# LED_Strips_-_Schematic.net
KiCad netlist of a schematic drawn in EAGLE
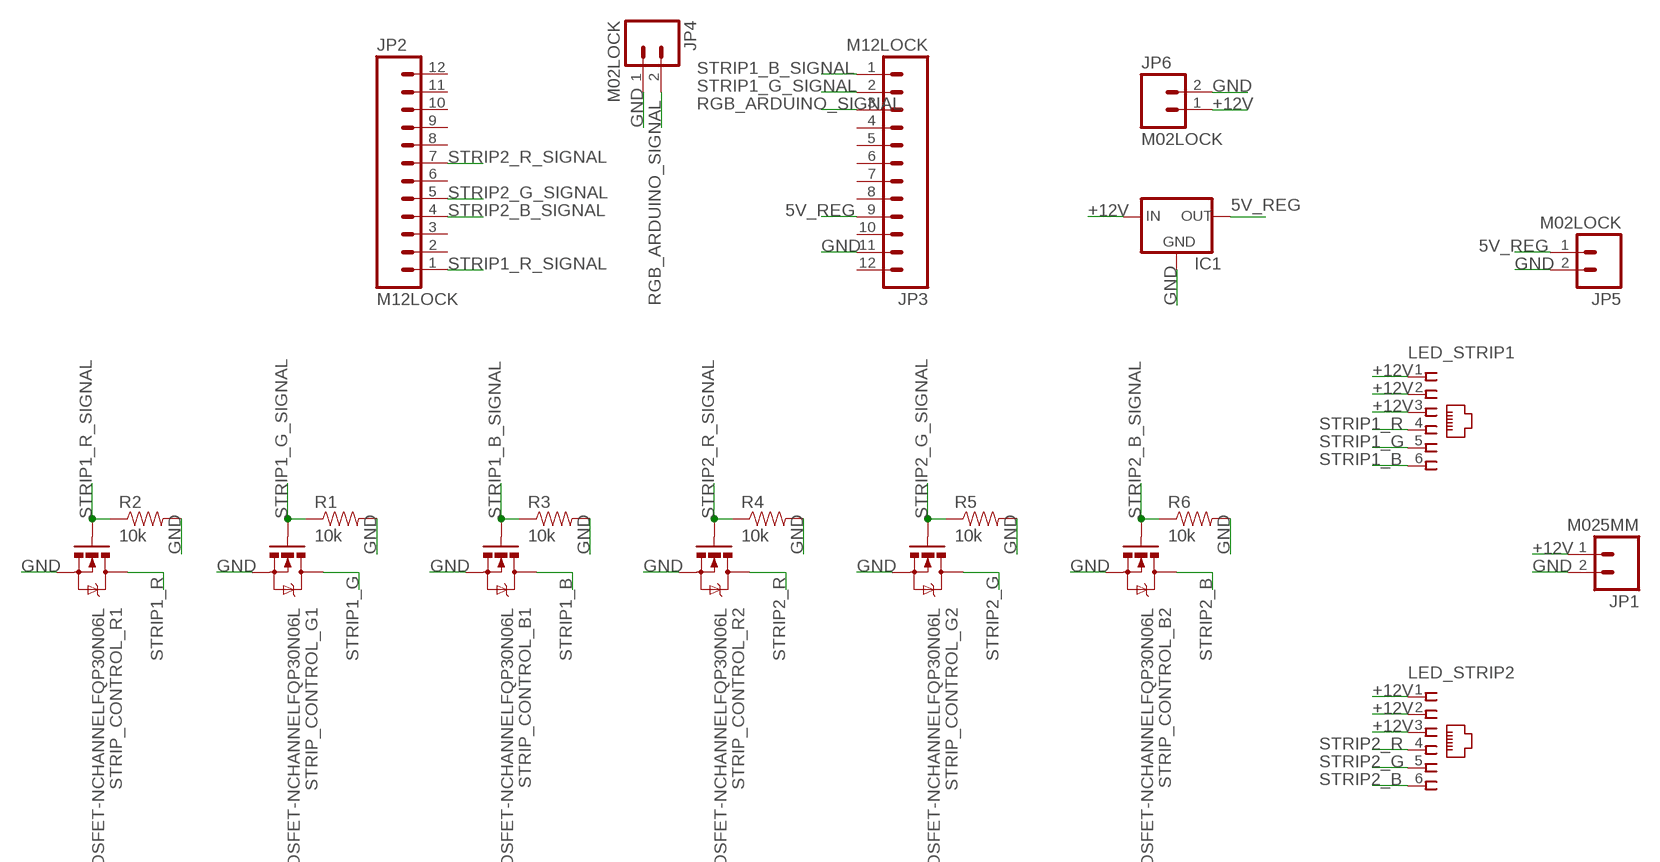
[diagram p0: schematic, sheet 1]

(export (version "E")
  (design (tool "Eeschema 10.0.6"))
  (components
    (comp (ref "IC1")
      (value "V_REG_78XXSIDE")
      (footprint "eagle-import:78XXL")
      (libsource (lib "eagle-import") (part "V_REG_78XXSIDE"))
    )
    (comp (ref "JP1")
      (value "M025MM")
      (footprint "eagle-import:SCREWTERMINAL-5MM-2")
      (libsource (lib "eagle-import") (part "M025MM"))
    )
    (comp (ref "JP2")
      (value "M12LOCK")
      (footprint "eagle-import:1X12_LOCK")
      (libsource (lib "eagle-import") (part "M12LOCK"))
    )
    (comp (ref "JP3")
      (value "M12LOCK")
      (footprint "eagle-import:1X12_LOCK")
      (libsource (lib "eagle-import") (part "M12LOCK"))
    )
    (comp (ref "JP4")
      (value "M02LOCK")
      (footprint "eagle-import:1X02_LOCK")
      (libsource (lib "eagle-import") (part "M02LOCK"))
    )
    (comp (ref "JP5")
      (value "M02LOCK")
      (footprint "eagle-import:1X02_LOCK")
      (libsource (lib "eagle-import") (part "M02LOCK"))
    )
    (comp (ref "JP6")
      (value "M02LOCK")
      (footprint "eagle-import:1X02_LOCK")
      (libsource (lib "eagle-import") (part "M02LOCK"))
    )
    (comp (ref "LED_STRIP1")
      (value "555165-1")
      (footprint "eagle-import:555165-1")
      (libsource (lib "eagle-import") (part "555165-1"))
    )
    (comp (ref "LED_STRIP2")
      (value "555165-1")
      (footprint "eagle-import:555165-1")
      (libsource (lib "eagle-import") (part "555165-1"))
    )
    (comp (ref "R1")
      (value "10k")
      (footprint "eagle-import:0603-RES")
      (libsource (lib "eagle-import") (part "RESISTOR0603"))
    )
    (comp (ref "R2")
      (value "10k")
      (footprint "eagle-import:0603-RES")
      (libsource (lib "eagle-import") (part "RESISTOR0603"))
    )
    (comp (ref "R3")
      (value "10k")
      (footprint "eagle-import:0603-RES")
      (libsource (lib "eagle-import") (part "RESISTOR0603"))
    )
    (comp (ref "R4")
      (value "10k")
      (footprint "eagle-import:0603-RES")
      (libsource (lib "eagle-import") (part "RESISTOR0603"))
    )
    (comp (ref "R5")
      (value "10k")
      (footprint "eagle-import:0603-RES")
      (libsource (lib "eagle-import") (part "RESISTOR0603"))
    )
    (comp (ref "R6")
      (value "10k")
      (footprint "eagle-import:0603-RES")
      (libsource (lib "eagle-import") (part "RESISTOR0603"))
    )
    (comp (ref "STRIP_CONTROL_B1")
      (value "MOSFET-NCHANNELFQP30N06L")
      (footprint "eagle-import:TO220V")
      (libsource (lib "eagle-import") (part "MOSFET-NCHANNELFQP30N06L"))
    )
    (comp (ref "STRIP_CONTROL_B2")
      (value "MOSFET-NCHANNELFQP30N06L")
      (footprint "eagle-import:TO220V")
      (libsource (lib "eagle-import") (part "MOSFET-NCHANNELFQP30N06L"))
    )
    (comp (ref "STRIP_CONTROL_G1")
      (value "MOSFET-NCHANNELFQP30N06L")
      (footprint "eagle-import:TO220V")
      (libsource (lib "eagle-import") (part "MOSFET-NCHANNELFQP30N06L"))
    )
    (comp (ref "STRIP_CONTROL_G2")
      (value "MOSFET-NCHANNELFQP30N06L")
      (footprint "eagle-import:TO220V")
      (libsource (lib "eagle-import") (part "MOSFET-NCHANNELFQP30N06L"))
    )
    (comp (ref "STRIP_CONTROL_R1")
      (value "MOSFET-NCHANNELFQP30N06L")
      (footprint "eagle-import:TO220V")
      (libsource (lib "eagle-import") (part "MOSFET-NCHANNELFQP30N06L"))
    )
    (comp (ref "STRIP_CONTROL_R2")
      (value "MOSFET-NCHANNELFQP30N06L")
      (footprint "eagle-import:TO220V")
      (libsource (lib "eagle-import") (part "MOSFET-NCHANNELFQP30N06L"))
    )
  )
  (nets
    (net (code "1") (name "/+12V") (class "Default")
      (node (ref "IC1") (pin "IN") (pinfunction "IN_IN") (pintype "input"))
      (node (ref "JP1") (pin "1") (pinfunction "1_1") (pintype "passive"))
      (node (ref "JP6") (pin "1") (pinfunction "1_1") (pintype "passive"))
      (node (ref "LED_STRIP1") (pin "1") (pinfunction "1_1") (pintype "passive"))
      (node (ref "LED_STRIP1") (pin "2") (pinfunction "2_2") (pintype "passive"))
      (node (ref "LED_STRIP1") (pin "3") (pinfunction "3_3") (pintype "passive"))
      (node (ref "LED_STRIP2") (pin "1") (pinfunction "1_1") (pintype "passive"))
      (node (ref "LED_STRIP2") (pin "2") (pinfunction "2_2") (pintype "passive"))
      (node (ref "LED_STRIP2") (pin "3") (pinfunction "3_3") (pintype "passive"))
    )
    (net (code "2") (name "/5V_REG") (class "Default")
      (node (ref "IC1") (pin "OUT") (pinfunction "OUT_OUT") (pintype "output"))
      (node (ref "JP3") (pin "9") (pinfunction "9_9") (pintype "passive"))
      (node (ref "JP5") (pin "1") (pinfunction "1_1") (pintype "passive"))
    )
    (net (code "3") (name "/GND") (class "Default")
      (node (ref "IC1") (pin "GND") (pinfunction "GND_GND") (pintype "input"))
      (node (ref "JP1") (pin "2") (pinfunction "2_2") (pintype "passive"))
      (node (ref "JP3") (pin "11") (pinfunction "11_11") (pintype "passive"))
      (node (ref "JP4") (pin "1") (pinfunction "1_1") (pintype "passive"))
      (node (ref "JP5") (pin "2") (pinfunction "2_2") (pintype "passive"))
      (node (ref "JP6") (pin "2") (pinfunction "2_2") (pintype "passive"))
      (node (ref "R1") (pin "2") (pinfunction "2_2") (pintype "passive"))
      (node (ref "R2") (pin "2") (pinfunction "2_2") (pintype "passive"))
      (node (ref "R3") (pin "2") (pinfunction "2_2") (pintype "passive"))
      (node (ref "R4") (pin "2") (pinfunction "2_2") (pintype "passive"))
      (node (ref "R5") (pin "2") (pinfunction "2_2") (pintype "passive"))
      (node (ref "R6") (pin "2") (pinfunction "2_2") (pintype "passive"))
      (node (ref "STRIP_CONTROL_B1") (pin "3") (pinfunction "S_3") (pintype "passive"))
      (node (ref "STRIP_CONTROL_B2") (pin "3") (pinfunction "S_3") (pintype "passive"))
      (node (ref "STRIP_CONTROL_G1") (pin "3") (pinfunction "S_3") (pintype "passive"))
      (node (ref "STRIP_CONTROL_G2") (pin "3") (pinfunction "S_3") (pintype "passive"))
      (node (ref "STRIP_CONTROL_R1") (pin "3") (pinfunction "S_3") (pintype "passive"))
      (node (ref "STRIP_CONTROL_R2") (pin "3") (pinfunction "S_3") (pintype "passive"))
    )
    (net (code "4") (name "/RGB_ARDUINO_SIGNAL") (class "Default")
      (node (ref "JP3") (pin "3") (pinfunction "3_3") (pintype "passive"))
      (node (ref "JP4") (pin "2") (pinfunction "2_2") (pintype "passive"))
    )
    (net (code "5") (name "/STRIP1_B") (class "Default")
      (node (ref "LED_STRIP1") (pin "6") (pinfunction "6_6") (pintype "passive"))
      (node (ref "STRIP_CONTROL_B1") (pin "2") (pinfunction "D_2") (pintype "passive"))
    )
    (net (code "6") (name "/STRIP1_B_SIGNAL") (class "Default")
      (node (ref "JP3") (pin "1") (pinfunction "1_1") (pintype "passive"))
      (node (ref "R3") (pin "1") (pinfunction "1_1") (pintype "passive"))
      (node (ref "STRIP_CONTROL_B1") (pin "1") (pinfunction "G_1") (pintype "passive"))
    )
    (net (code "7") (name "/STRIP1_G") (class "Default")
      (node (ref "LED_STRIP1") (pin "5") (pinfunction "5_5") (pintype "passive"))
      (node (ref "STRIP_CONTROL_G1") (pin "2") (pinfunction "D_2") (pintype "passive"))
    )
    (net (code "8") (name "/STRIP1_G_SIGNAL") (class "Default")
      (node (ref "JP3") (pin "2") (pinfunction "2_2") (pintype "passive"))
      (node (ref "R1") (pin "1") (pinfunction "1_1") (pintype "passive"))
      (node (ref "STRIP_CONTROL_G1") (pin "1") (pinfunction "G_1") (pintype "passive"))
    )
    (net (code "9") (name "/STRIP1_R") (class "Default")
      (node (ref "LED_STRIP1") (pin "4") (pinfunction "4_4") (pintype "passive"))
      (node (ref "STRIP_CONTROL_R1") (pin "2") (pinfunction "D_2") (pintype "passive"))
    )
    (net (code "10") (name "/STRIP1_R_SIGNAL") (class "Default")
      (node (ref "JP2") (pin "1") (pinfunction "1_1") (pintype "passive"))
      (node (ref "R2") (pin "1") (pinfunction "1_1") (pintype "passive"))
      (node (ref "STRIP_CONTROL_R1") (pin "1") (pinfunction "G_1") (pintype "passive"))
    )
    (net (code "11") (name "/STRIP2_B") (class "Default")
      (node (ref "LED_STRIP2") (pin "6") (pinfunction "6_6") (pintype "passive"))
      (node (ref "STRIP_CONTROL_B2") (pin "2") (pinfunction "D_2") (pintype "passive"))
    )
    (net (code "12") (name "/STRIP2_B_SIGNAL") (class "Default")
      (node (ref "JP2") (pin "4") (pinfunction "4_4") (pintype "passive"))
      (node (ref "R6") (pin "1") (pinfunction "1_1") (pintype "passive"))
      (node (ref "STRIP_CONTROL_B2") (pin "1") (pinfunction "G_1") (pintype "passive"))
    )
    (net (code "13") (name "/STRIP2_G") (class "Default")
      (node (ref "LED_STRIP2") (pin "5") (pinfunction "5_5") (pintype "passive"))
      (node (ref "STRIP_CONTROL_G2") (pin "2") (pinfunction "D_2") (pintype "passive"))
    )
    (net (code "14") (name "/STRIP2_G_SIGNAL") (class "Default")
      (node (ref "JP2") (pin "5") (pinfunction "5_5") (pintype "passive"))
      (node (ref "R5") (pin "1") (pinfunction "1_1") (pintype "passive"))
      (node (ref "STRIP_CONTROL_G2") (pin "1") (pinfunction "G_1") (pintype "passive"))
    )
    (net (code "15") (name "/STRIP2_R") (class "Default")
      (node (ref "LED_STRIP2") (pin "4") (pinfunction "4_4") (pintype "passive"))
      (node (ref "STRIP_CONTROL_R2") (pin "2") (pinfunction "D_2") (pintype "passive"))
    )
    (net (code "16") (name "/STRIP2_R_SIGNAL") (class "Default")
      (node (ref "JP2") (pin "7") (pinfunction "7_7") (pintype "passive"))
      (node (ref "R4") (pin "1") (pinfunction "1_1") (pintype "passive"))
      (node (ref "STRIP_CONTROL_R2") (pin "1") (pinfunction "G_1") (pintype "passive"))
    )
    (net (code "17") (name "unconnected-(JP2-Pad2)") (class "Default")
      (node (ref "JP2") (pin "2") (pinfunction "2_2") (pintype "passive"))
    )
    (net (code "18") (name "unconnected-(JP2-Pad3)") (class "Default")
      (node (ref "JP2") (pin "3") (pinfunction "3_3") (pintype "passive"))
    )
    (net (code "19") (name "unconnected-(JP2-Pad6)") (class "Default")
      (node (ref "JP2") (pin "6") (pinfunction "6_6") (pintype "passive"))
    )
    (net (code "20") (name "unconnected-(JP2-Pad8)") (class "Default")
      (node (ref "JP2") (pin "8") (pinfunction "8_8") (pintype "passive"))
    )
    (net (code "21") (name "unconnected-(JP2-Pad9)") (class "Default")
      (node (ref "JP2") (pin "9") (pinfunction "9_9") (pintype "passive"))
    )
    (net (code "22") (name "unconnected-(JP2-Pad10)") (class "Default")
      (node (ref "JP2") (pin "10") (pinfunction "10_10") (pintype "passive"))
    )
    (net (code "23") (name "unconnected-(JP2-Pad11)") (class "Default")
      (node (ref "JP2") (pin "11") (pinfunction "11_11") (pintype "passive"))
    )
    (net (code "24") (name "unconnected-(JP2-Pad12)") (class "Default")
      (node (ref "JP2") (pin "12") (pinfunction "12_12") (pintype "passive"))
    )
    (net (code "25") (name "unconnected-(JP3-Pad4)") (class "Default")
      (node (ref "JP3") (pin "4") (pinfunction "4_4") (pintype "passive"))
    )
    (net (code "26") (name "unconnected-(JP3-Pad5)") (class "Default")
      (node (ref "JP3") (pin "5") (pinfunction "5_5") (pintype "passive"))
    )
    (net (code "27") (name "unconnected-(JP3-Pad6)") (class "Default")
      (node (ref "JP3") (pin "6") (pinfunction "6_6") (pintype "passive"))
    )
    (net (code "28") (name "unconnected-(JP3-Pad7)") (class "Default")
      (node (ref "JP3") (pin "7") (pinfunction "7_7") (pintype "passive"))
    )
    (net (code "29") (name "unconnected-(JP3-Pad8)") (class "Default")
      (node (ref "JP3") (pin "8") (pinfunction "8_8") (pintype "passive"))
    )
    (net (code "30") (name "unconnected-(JP3-Pad10)") (class "Default")
      (node (ref "JP3") (pin "10") (pinfunction "10_10") (pintype "passive"))
    )
    (net (code "31") (name "unconnected-(JP3-Pad12)") (class "Default")
      (node (ref "JP3") (pin "12") (pinfunction "12_12") (pintype "passive"))
    )
  )
)
